# SCH_homework2_2025-05-07.net
KiCad netlist of a schematic drawn in EasyEDA
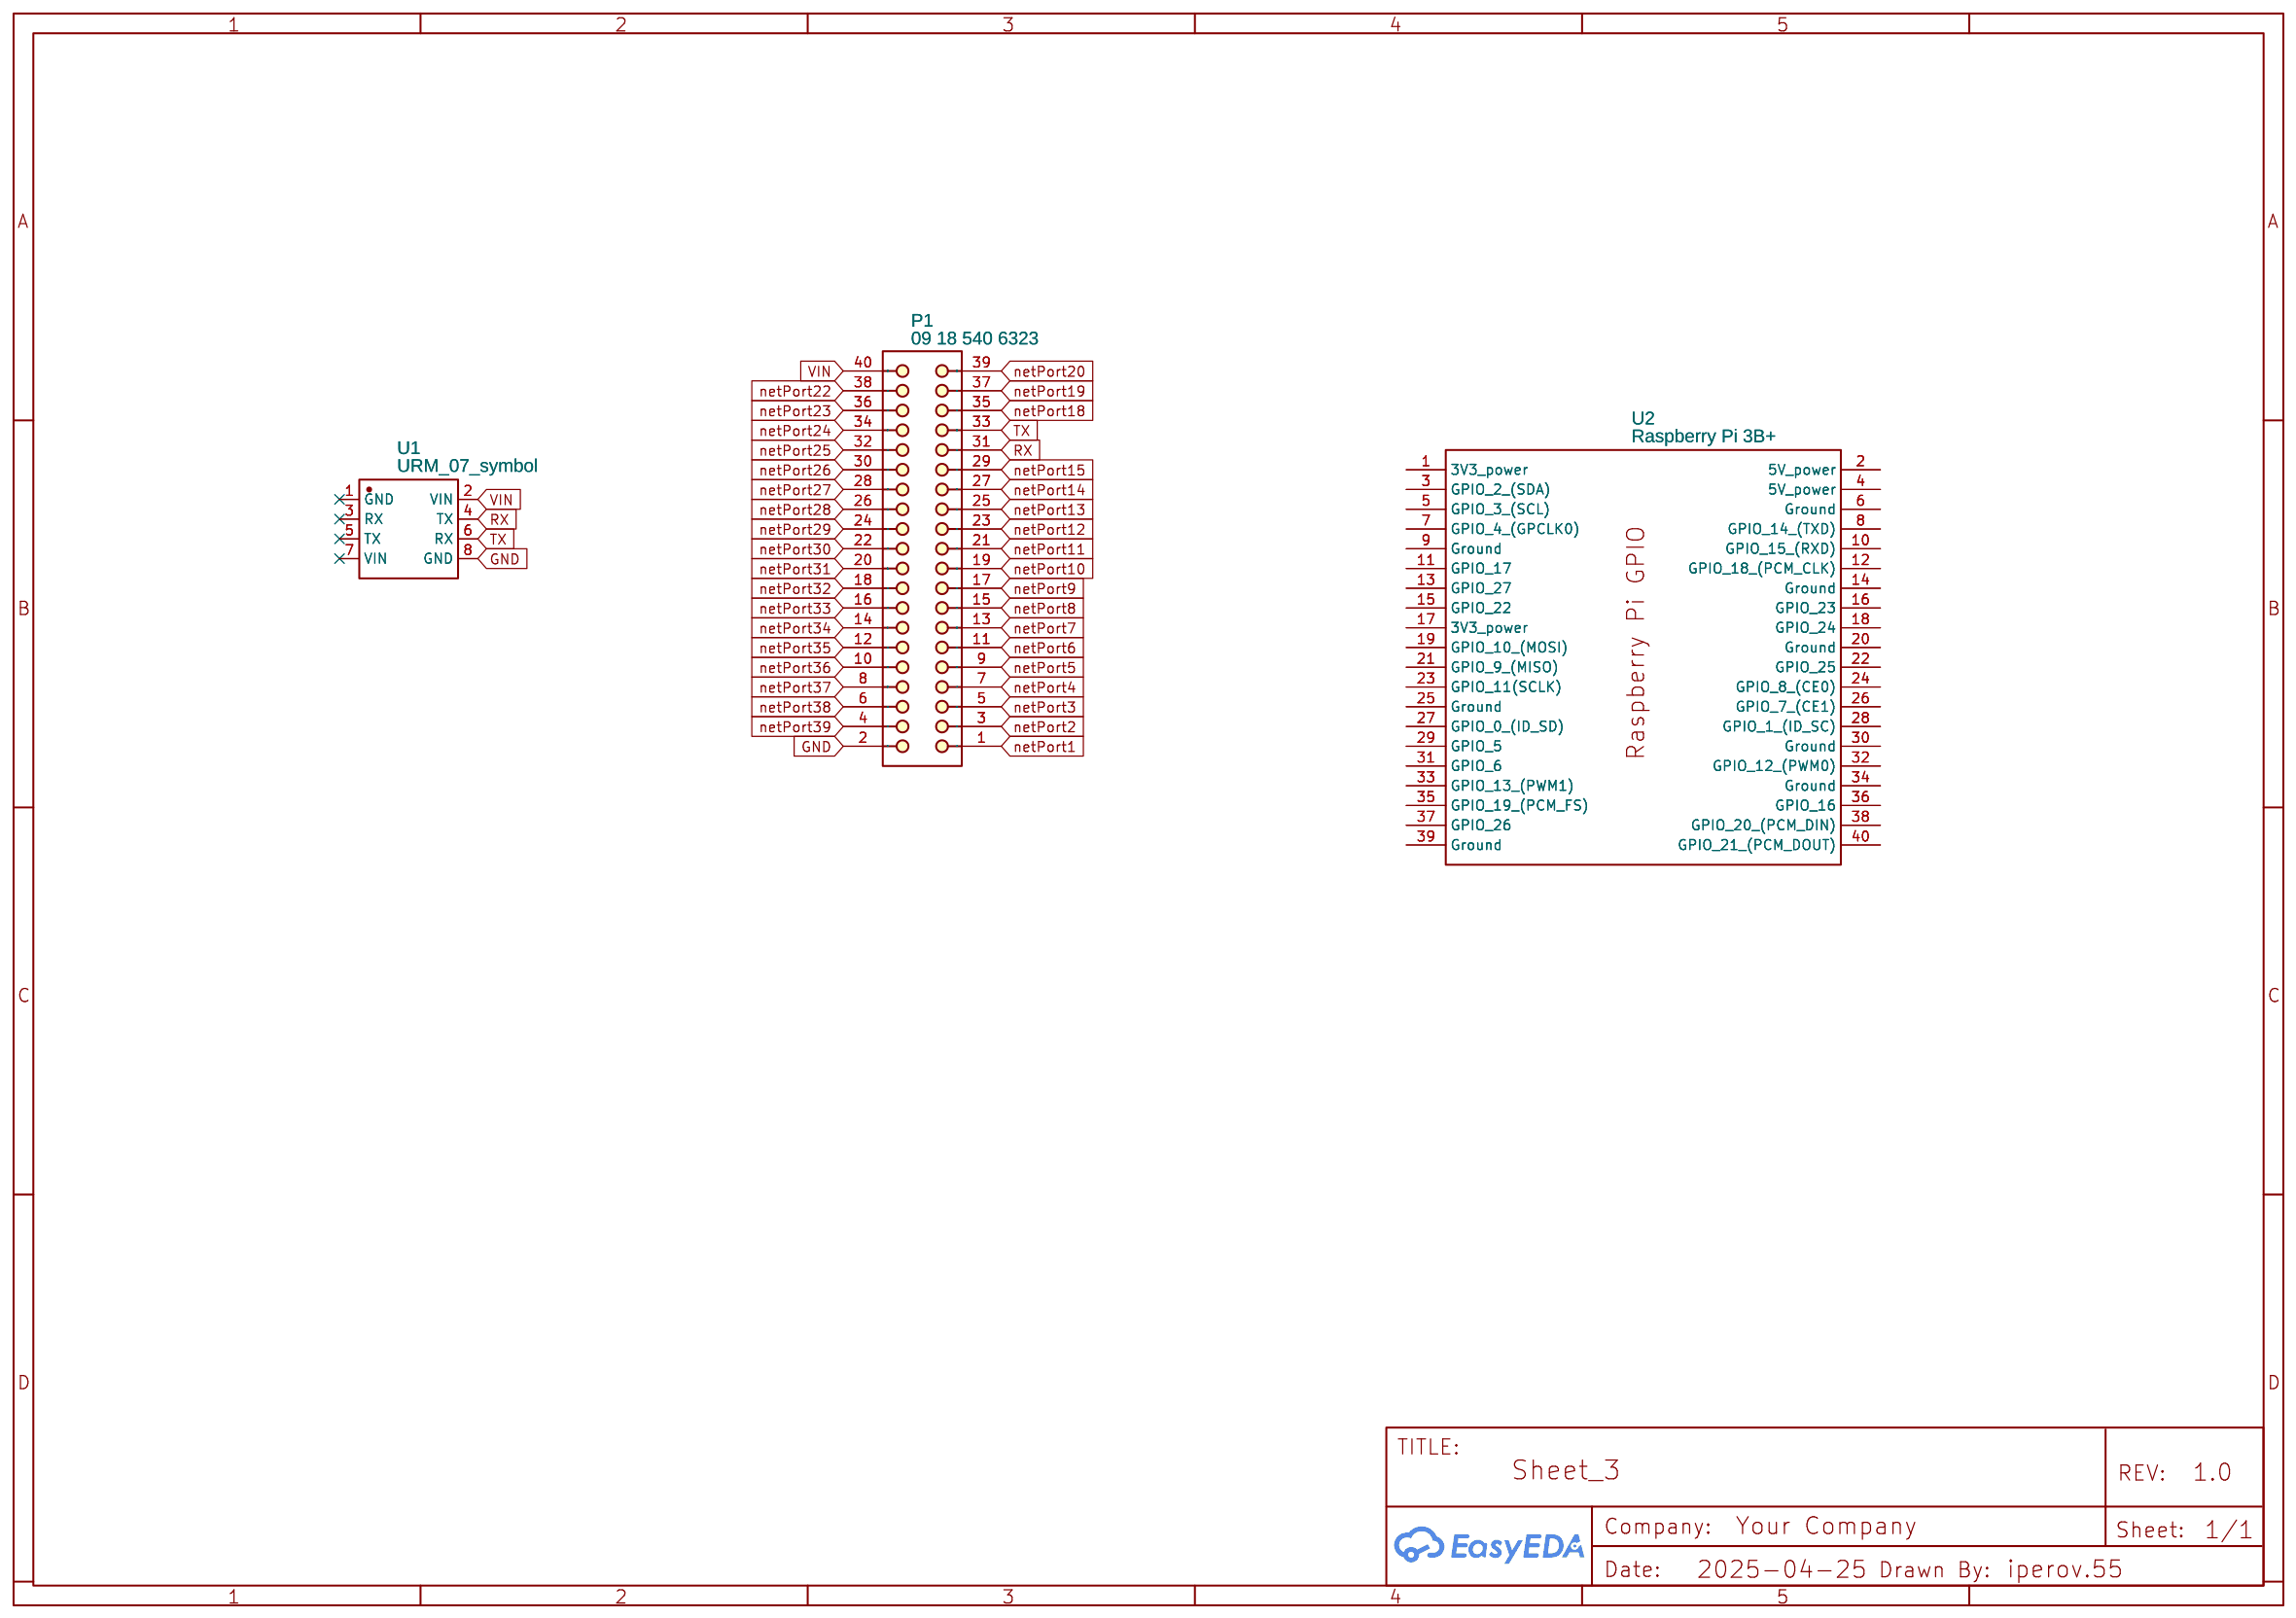
[diagram p0: schematic sheet]

(export (version "E")
  (design (tool "Eeschema 10.0.6"))
  (components
    (comp (ref "P1") (value "09 18 540 6323") (libsource (lib "") (part "09 18 540 6323")))
    (comp (ref "U1") (value "URM_07_symbol") (libsource (lib "") (part "URM_07_symbol")))
    (comp (ref "U2") (value "Raspberry Pi 3B+") (libsource (lib "") (part "Raspberry Pi 3B+")))
  )
  (nets
    (net (code "1") (name "GND") (class "Default")
      (node (ref "P1") (pin "2") (pinfunction "2_2") (pintype "unspecified"))
      (node (ref "U1") (pin "8") (pinfunction "GND_8") (pintype "unspecified"))
    )
    (net (code "2") (name "RX") (class "Default")
      (node (ref "P1") (pin "31") (pinfunction "31_31") (pintype "unspecified"))
      (node (ref "U1") (pin "4") (pinfunction "TX_4") (pintype "unspecified"))
    )
    (net (code "3") (name "TX") (class "Default")
      (node (ref "P1") (pin "33") (pinfunction "33_33") (pintype "unspecified"))
      (node (ref "U1") (pin "6") (pinfunction "RX_6") (pintype "unspecified"))
    )
    (net (code "4") (name "VIN") (class "Default")
      (node (ref "P1") (pin "40") (pinfunction "40_40") (pintype "unspecified"))
      (node (ref "U1") (pin "2") (pinfunction "VIN_2") (pintype "unspecified"))
    )
    (net (code "5") (name "netPort1") (class "Default")
      (node (ref "P1") (pin "1") (pinfunction "1_1") (pintype "unspecified"))
    )
    (net (code "6") (name "netPort2") (class "Default")
      (node (ref "P1") (pin "3") (pinfunction "3_3") (pintype "unspecified"))
    )
    (net (code "7") (name "netPort3") (class "Default")
      (node (ref "P1") (pin "5") (pinfunction "5_5") (pintype "unspecified"))
    )
    (net (code "8") (name "netPort4") (class "Default")
      (node (ref "P1") (pin "7") (pinfunction "7_7") (pintype "unspecified"))
    )
    (net (code "9") (name "netPort5") (class "Default")
      (node (ref "P1") (pin "9") (pinfunction "9_9") (pintype "unspecified"))
    )
    (net (code "10") (name "netPort6") (class "Default")
      (node (ref "P1") (pin "11") (pinfunction "11_11") (pintype "unspecified"))
    )
    (net (code "11") (name "netPort7") (class "Default")
      (node (ref "P1") (pin "13") (pinfunction "13_13") (pintype "unspecified"))
    )
    (net (code "12") (name "netPort8") (class "Default")
      (node (ref "P1") (pin "15") (pinfunction "15_15") (pintype "unspecified"))
    )
    (net (code "13") (name "netPort9") (class "Default")
      (node (ref "P1") (pin "17") (pinfunction "17_17") (pintype "unspecified"))
    )
    (net (code "14") (name "netPort10") (class "Default")
      (node (ref "P1") (pin "19") (pinfunction "19_19") (pintype "unspecified"))
    )
    (net (code "15") (name "netPort11") (class "Default")
      (node (ref "P1") (pin "21") (pinfunction "21_21") (pintype "unspecified"))
    )
    (net (code "16") (name "netPort12") (class "Default")
      (node (ref "P1") (pin "23") (pinfunction "23_23") (pintype "unspecified"))
    )
    (net (code "17") (name "netPort13") (class "Default")
      (node (ref "P1") (pin "25") (pinfunction "25_25") (pintype "unspecified"))
    )
    (net (code "18") (name "netPort14") (class "Default")
      (node (ref "P1") (pin "27") (pinfunction "27_27") (pintype "unspecified"))
    )
    (net (code "19") (name "netPort15") (class "Default")
      (node (ref "P1") (pin "29") (pinfunction "29_29") (pintype "unspecified"))
    )
    (net (code "20") (name "netPort18") (class "Default")
      (node (ref "P1") (pin "35") (pinfunction "35_35") (pintype "unspecified"))
    )
    (net (code "21") (name "netPort19") (class "Default")
      (node (ref "P1") (pin "37") (pinfunction "37_37") (pintype "unspecified"))
    )
    (net (code "22") (name "netPort20") (class "Default")
      (node (ref "P1") (pin "39") (pinfunction "39_39") (pintype "unspecified"))
    )
    (net (code "23") (name "netPort22") (class "Default")
      (node (ref "P1") (pin "38") (pinfunction "38_38") (pintype "unspecified"))
    )
    (net (code "24") (name "netPort23") (class "Default")
      (node (ref "P1") (pin "36") (pinfunction "36_36") (pintype "unspecified"))
    )
    (net (code "25") (name "netPort24") (class "Default")
      (node (ref "P1") (pin "34") (pinfunction "34_34") (pintype "unspecified"))
    )
    (net (code "26") (name "netPort25") (class "Default")
      (node (ref "P1") (pin "32") (pinfunction "32_32") (pintype "unspecified"))
    )
    (net (code "27") (name "netPort26") (class "Default")
      (node (ref "P1") (pin "30") (pinfunction "30_30") (pintype "unspecified"))
    )
    (net (code "28") (name "netPort27") (class "Default")
      (node (ref "P1") (pin "28") (pinfunction "28_28") (pintype "unspecified"))
    )
    (net (code "29") (name "netPort28") (class "Default")
      (node (ref "P1") (pin "26") (pinfunction "26_26") (pintype "unspecified"))
    )
    (net (code "30") (name "netPort29") (class "Default")
      (node (ref "P1") (pin "24") (pinfunction "24_24") (pintype "unspecified"))
    )
    (net (code "31") (name "netPort30") (class "Default")
      (node (ref "P1") (pin "22") (pinfunction "22_22") (pintype "unspecified"))
    )
    (net (code "32") (name "netPort31") (class "Default")
      (node (ref "P1") (pin "20") (pinfunction "20_20") (pintype "unspecified"))
    )
    (net (code "33") (name "netPort32") (class "Default")
      (node (ref "P1") (pin "18") (pinfunction "18_18") (pintype "unspecified"))
    )
    (net (code "34") (name "netPort33") (class "Default")
      (node (ref "P1") (pin "16") (pinfunction "16_16") (pintype "unspecified"))
    )
    (net (code "35") (name "netPort34") (class "Default")
      (node (ref "P1") (pin "14") (pinfunction "14_14") (pintype "unspecified"))
    )
    (net (code "36") (name "netPort35") (class "Default")
      (node (ref "P1") (pin "12") (pinfunction "12_12") (pintype "unspecified"))
    )
    (net (code "37") (name "netPort36") (class "Default")
      (node (ref "P1") (pin "10") (pinfunction "10_10") (pintype "unspecified"))
    )
    (net (code "38") (name "netPort37") (class "Default")
      (node (ref "P1") (pin "8") (pinfunction "8_8") (pintype "unspecified"))
    )
    (net (code "39") (name "netPort38") (class "Default")
      (node (ref "P1") (pin "6") (pinfunction "6_6") (pintype "unspecified"))
    )
    (net (code "40") (name "netPort39") (class "Default")
      (node (ref "P1") (pin "4") (pinfunction "4_4") (pintype "unspecified"))
    )
    (net (code "41") (name "unconnected-(U1-GND-Pad1)") (class "Default")
      (node (ref "U1") (pin "1") (pinfunction "GND_1") (pintype "unspecified+no_connect"))
    )
    (net (code "42") (name "unconnected-(U1-RX-Pad3)") (class "Default")
      (node (ref "U1") (pin "3") (pinfunction "RX_3") (pintype "unspecified+no_connect"))
    )
    (net (code "43") (name "unconnected-(U1-TX-Pad5)") (class "Default")
      (node (ref "U1") (pin "5") (pinfunction "TX_5") (pintype "unspecified+no_connect"))
    )
    (net (code "44") (name "unconnected-(U1-VIN-Pad7)") (class "Default")
      (node (ref "U1") (pin "7") (pinfunction "VIN_7") (pintype "unspecified+no_connect"))
    )
    (net (code "45") (name "unconnected-(U2-3V3_power-Pad1)") (class "Default")
      (node (ref "U2") (pin "1") (pinfunction "3V3_power_1") (pintype "passive"))
    )
    (net (code "46") (name "unconnected-(U2-3V3_power-Pad17)") (class "Default")
      (node (ref "U2") (pin "17") (pinfunction "3V3_power_17") (pintype "passive"))
    )
    (net (code "47") (name "unconnected-(U2-5V_power-Pad2)") (class "Default")
      (node (ref "U2") (pin "2") (pinfunction "5V_power_2") (pintype "passive"))
    )
    (net (code "48") (name "unconnected-(U2-5V_power-Pad4)") (class "Default")
      (node (ref "U2") (pin "4") (pinfunction "5V_power_4") (pintype "passive"))
    )
    (net (code "49") (name "unconnected-(U2-GPIO_0_(ID_SD)-Pad27)") (class "Default")
      (node (ref "U2") (pin "27") (pinfunction "GPIO_0_(ID_SD)_27") (pintype "unspecified"))
    )
    (net (code "50") (name "unconnected-(U2-GPIO_1_(ID_SC)-Pad28)") (class "Default")
      (node (ref "U2") (pin "28") (pinfunction "GPIO_1_(ID_SC)_28") (pintype "unspecified"))
    )
    (net (code "51") (name "unconnected-(U2-GPIO_2_(SDA)-Pad3)") (class "Default")
      (node (ref "U2") (pin "3") (pinfunction "GPIO_2_(SDA)_3") (pintype "unspecified"))
    )
    (net (code "52") (name "unconnected-(U2-GPIO_3_(SCL)-Pad5)") (class "Default")
      (node (ref "U2") (pin "5") (pinfunction "GPIO_3_(SCL)_5") (pintype "unspecified"))
    )
    (net (code "53") (name "unconnected-(U2-GPIO_4_(GPCLK0)-Pad7)") (class "Default")
      (node (ref "U2") (pin "7") (pinfunction "GPIO_4_(GPCLK0)_7") (pintype "unspecified"))
    )
    (net (code "54") (name "unconnected-(U2-GPIO_5-Pad29)") (class "Default")
      (node (ref "U2") (pin "29") (pinfunction "GPIO_5_29") (pintype "unspecified"))
    )
    (net (code "55") (name "unconnected-(U2-GPIO_6-Pad31)") (class "Default")
      (node (ref "U2") (pin "31") (pinfunction "GPIO_6_31") (pintype "unspecified"))
    )
    (net (code "56") (name "unconnected-(U2-GPIO_7_(CE1)-Pad26)") (class "Default")
      (node (ref "U2") (pin "26") (pinfunction "GPIO_7_(CE1)_26") (pintype "unspecified"))
    )
    (net (code "57") (name "unconnected-(U2-GPIO_8_(CE0)-Pad24)") (class "Default")
      (node (ref "U2") (pin "24") (pinfunction "GPIO_8_(CE0)_24") (pintype "unspecified"))
    )
    (net (code "58") (name "unconnected-(U2-GPIO_9_(MISO)-Pad21)") (class "Default")
      (node (ref "U2") (pin "21") (pinfunction "GPIO_9_(MISO)_21") (pintype "unspecified"))
    )
    (net (code "59") (name "unconnected-(U2-GPIO_10_(MOSI)-Pad19)") (class "Default")
      (node (ref "U2") (pin "19") (pinfunction "GPIO_10_(MOSI)_19") (pintype "unspecified"))
    )
    (net (code "60") (name "unconnected-(U2-GPIO_11(SCLK)-Pad23)") (class "Default")
      (node (ref "U2") (pin "23") (pinfunction "GPIO_11(SCLK)_23") (pintype "unspecified"))
    )
    (net (code "61") (name "unconnected-(U2-GPIO_12_(PWM0)-Pad32)") (class "Default")
      (node (ref "U2") (pin "32") (pinfunction "GPIO_12_(PWM0)_32") (pintype "unspecified"))
    )
    (net (code "62") (name "unconnected-(U2-GPIO_13_(PWM1)-Pad33)") (class "Default")
      (node (ref "U2") (pin "33") (pinfunction "GPIO_13_(PWM1)_33") (pintype "unspecified"))
    )
    (net (code "63") (name "unconnected-(U2-GPIO_14_(TXD)-Pad8)") (class "Default")
      (node (ref "U2") (pin "8") (pinfunction "GPIO_14_(TXD)_8") (pintype "unspecified"))
    )
    (net (code "64") (name "unconnected-(U2-GPIO_15_(RXD)-Pad10)") (class "Default")
      (node (ref "U2") (pin "10") (pinfunction "GPIO_15_(RXD)_10") (pintype "unspecified"))
    )
    (net (code "65") (name "unconnected-(U2-GPIO_16-Pad36)") (class "Default")
      (node (ref "U2") (pin "36") (pinfunction "GPIO_16_36") (pintype "unspecified"))
    )
    (net (code "66") (name "unconnected-(U2-GPIO_17-Pad11)") (class "Default")
      (node (ref "U2") (pin "11") (pinfunction "GPIO_17_11") (pintype "unspecified"))
    )
    (net (code "67") (name "unconnected-(U2-GPIO_18_(PCM_CLK)-Pad12)") (class "Default")
      (node (ref "U2") (pin "12") (pinfunction "GPIO_18_(PCM_CLK)_12") (pintype "unspecified"))
    )
    (net (code "68") (name "unconnected-(U2-GPIO_19_(PCM_FS)-Pad35)") (class "Default")
      (node (ref "U2") (pin "35") (pinfunction "GPIO_19_(PCM_FS)_35") (pintype "unspecified"))
    )
    (net (code "69") (name "unconnected-(U2-GPIO_20_(PCM_DIN)-Pad38)") (class "Default")
      (node (ref "U2") (pin "38") (pinfunction "GPIO_20_(PCM_DIN)_38") (pintype "unspecified"))
    )
    (net (code "70") (name "unconnected-(U2-GPIO_21_(PCM_DOUT)-Pad40)") (class "Default")
      (node (ref "U2") (pin "40") (pinfunction "GPIO_21_(PCM_DOUT)_40") (pintype "unspecified"))
    )
    (net (code "71") (name "unconnected-(U2-GPIO_22-Pad15)") (class "Default")
      (node (ref "U2") (pin "15") (pinfunction "GPIO_22_15") (pintype "unspecified"))
    )
    (net (code "72") (name "unconnected-(U2-GPIO_23-Pad16)") (class "Default")
      (node (ref "U2") (pin "16") (pinfunction "GPIO_23_16") (pintype "unspecified"))
    )
    (net (code "73") (name "unconnected-(U2-GPIO_24-Pad18)") (class "Default")
      (node (ref "U2") (pin "18") (pinfunction "GPIO_24_18") (pintype "unspecified"))
    )
    (net (code "74") (name "unconnected-(U2-GPIO_25-Pad22)") (class "Default")
      (node (ref "U2") (pin "22") (pinfunction "GPIO_25_22") (pintype "unspecified"))
    )
    (net (code "75") (name "unconnected-(U2-GPIO_26-Pad37)") (class "Default")
      (node (ref "U2") (pin "37") (pinfunction "GPIO_26_37") (pintype "unspecified"))
    )
    (net (code "76") (name "unconnected-(U2-GPIO_27-Pad13)") (class "Default")
      (node (ref "U2") (pin "13") (pinfunction "GPIO_27_13") (pintype "unspecified"))
    )
    (net (code "77") (name "unconnected-(U2-Ground-Pad6)") (class "Default")
      (node (ref "U2") (pin "6") (pinfunction "Ground_6") (pintype "unspecified"))
    )
    (net (code "78") (name "unconnected-(U2-Ground-Pad9)") (class "Default")
      (node (ref "U2") (pin "9") (pinfunction "Ground_9") (pintype "unspecified"))
    )
    (net (code "79") (name "unconnected-(U2-Ground-Pad14)") (class "Default")
      (node (ref "U2") (pin "14") (pinfunction "Ground_14") (pintype "unspecified"))
    )
    (net (code "80") (name "unconnected-(U2-Ground-Pad20)") (class "Default")
      (node (ref "U2") (pin "20") (pinfunction "Ground_20") (pintype "unspecified"))
    )
    (net (code "81") (name "unconnected-(U2-Ground-Pad25)") (class "Default")
      (node (ref "U2") (pin "25") (pinfunction "Ground_25") (pintype "unspecified"))
    )
    (net (code "82") (name "unconnected-(U2-Ground-Pad30)") (class "Default")
      (node (ref "U2") (pin "30") (pinfunction "Ground_30") (pintype "unspecified"))
    )
    (net (code "83") (name "unconnected-(U2-Ground-Pad34)") (class "Default")
      (node (ref "U2") (pin "34") (pinfunction "Ground_34") (pintype "unspecified"))
    )
    (net (code "84") (name "unconnected-(U2-Ground-Pad39)") (class "Default")
      (node (ref "U2") (pin "39") (pinfunction "Ground_39") (pintype "unspecified"))
    )
  )
)
